# KORUZA_RPi_shield_power.net
KiCad netlist of a schematic drawn in Altium Designer
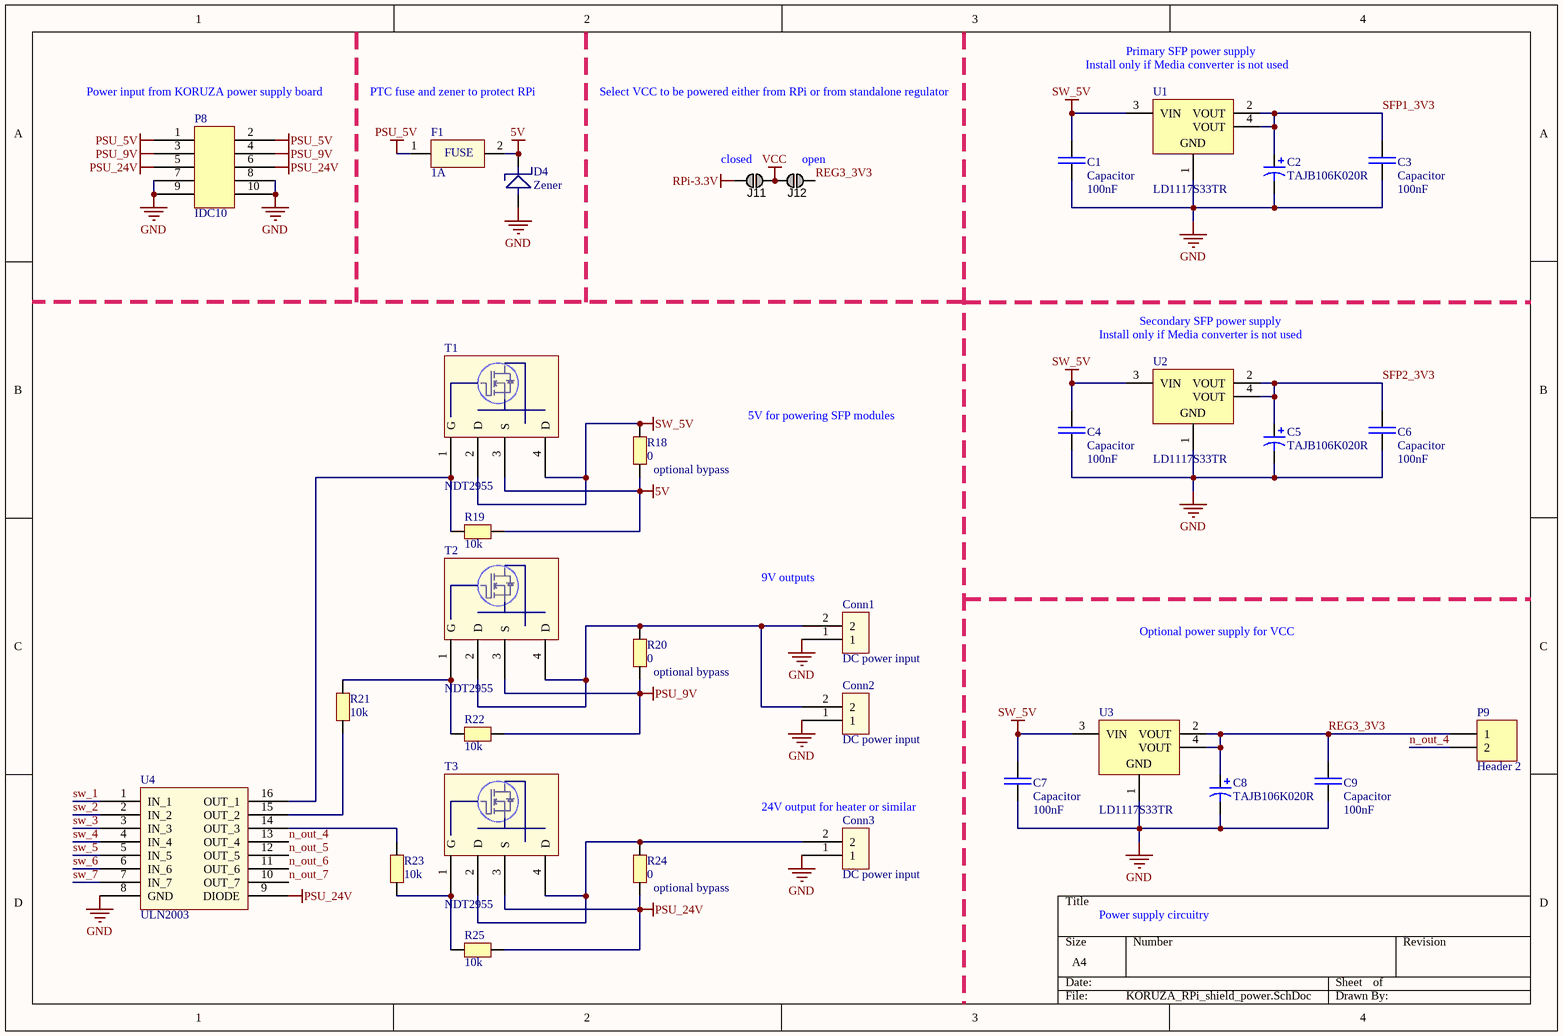
[diagram p0: KORUZA_RPi_shield_power.SchDoc]

(export (version "E")
  (design (tool "Eeschema 10.0.6"))
  (components
    (comp (ref "C1")
      (value "Capacitor")
      (footprint "0603")
      (description "General capacitor")
      (fields (field (name "ALTIUM_VALUE") "100nF"))
      (libsource (lib "GeneralComponents") (part "Capacitor"))
    )
    (comp (ref "C2")
      (value "TAJB106K020R")
      (footprint "AVX-CAPC3528_V")
      (description "Capacitor, Tantalum, 10uF 10% 20V MCCT-B (3528)")
      (fields (field (name "MANUFACTURER") "AVX") (field (name "TOLERANCE") "10%"))
      (libsource (lib "Altium Content Vault") (part "CMP-0279-00001-1"))
    )
    (comp (ref "C3")
      (value "Capacitor")
      (footprint "0603")
      (description "General capacitor")
      (fields (field (name "ALTIUM_VALUE") "100nF"))
      (libsource (lib "GeneralComponents") (part "Capacitor"))
    )
    (comp (ref "C4")
      (value "Capacitor")
      (footprint "0603")
      (description "General capacitor")
      (fields (field (name "ALTIUM_VALUE") "100nF"))
      (libsource (lib "GeneralComponents") (part "Capacitor"))
    )
    (comp (ref "C5")
      (value "TAJB106K020R")
      (footprint "AVX-CAPC3528_V")
      (description "Capacitor, Tantalum, 10uF 10% 20V MCCT-B (3528)")
      (fields (field (name "MANUFACTURER") "AVX") (field (name "TOLERANCE") "10%"))
      (libsource (lib "Altium Content Vault") (part "CMP-0279-00001-1"))
    )
    (comp (ref "C6")
      (value "Capacitor")
      (footprint "0603")
      (description "General capacitor")
      (fields (field (name "ALTIUM_VALUE") "100nF"))
      (libsource (lib "GeneralComponents") (part "Capacitor"))
    )
    (comp (ref "C7")
      (value "Capacitor")
      (footprint "0603")
      (description "General capacitor")
      (fields (field (name "ALTIUM_VALUE") "100nF"))
      (libsource (lib "GeneralComponents") (part "Capacitor"))
    )
    (comp (ref "C8")
      (value "TAJB106K020R")
      (footprint "AVX-CAPC3528_V")
      (description "Capacitor, Tantalum, 10uF 10% 20V MCCT-B (3528)")
      (fields (field (name "MANUFACTURER") "AVX") (field (name "TOLERANCE") "10%"))
      (libsource (lib "Altium Content Vault") (part "CMP-0279-00001-1"))
    )
    (comp (ref "C9")
      (value "Capacitor")
      (footprint "0603")
      (description "General capacitor")
      (fields (field (name "ALTIUM_VALUE") "100nF"))
      (libsource (lib "GeneralComponents") (part "Capacitor"))
    )
    (comp (ref "Conn1")
      (value "DC power input")
      (footprint "MKDSN 2,5/ 2-5,08 and powercon")
      (libsource (lib "GeneralComponents") (part "PowerScrewTerminal"))
    )
    (comp (ref "Conn2")
      (value "DC power input")
      (footprint "MKDSN 2,5/ 2-5,08 and powercon")
      (libsource (lib "GeneralComponents") (part "PowerScrewTerminal"))
    )
    (comp (ref "Conn3")
      (value "DC power input")
      (footprint "MKDSN 2,5/ 2-5,08 and powercon")
      (libsource (lib "GeneralComponents") (part "PowerScrewTerminal"))
    )
    (comp (ref "D4")
      (value "Zener")
      (footprint "DIOMELF3517N")
      (libsource (lib "GeneralComponents") (part "Zener"))
    )
    (comp (ref "F1")
      (value "1A")
      (footprint "1210")
      (description "1A fuse")
      (libsource (lib "GeneralComponents") (part "Fuse"))
    )
    (comp (ref "J11")
      (value "Jumper")
      (footprint "JUMP1")
      (description "SMD jumper")
      (libsource (lib "Misc") (part "JUMP1"))
    )
    (comp (ref "J12")
      (value "Jumper")
      (footprint "JUMP1")
      (description "SMD jumper")
      (libsource (lib "Misc") (part "JUMP1"))
    )
    (comp (ref "P8")
      (value "IDC10")
      (footprint "IDC10")
      (description "IDC 10pin")
      (libsource (lib "GeneralComponents") (part "IDC10"))
    )
    (comp (ref "P9")
      (value "Header 2")
      (footprint "HDR1X2")
      (description "Header, 2-Pin")
      (fields (field (name "PUBLISHER") "Altium Limited"))
      (libsource (lib "Miscellaneous Connectors") (part "Header 2"))
    )
    (comp (ref "R18")
      (value "0")
      (footprint "RESC2012X06N")
      (description "Resistor 0805 smd")
      (libsource (lib "") (part "Resistor_1"))
    )
    (comp (ref "R19")
      (value "10k")
      (footprint "RESC2012X06N")
      (description "Resistor 0805 smd")
      (libsource (lib "GeneralComponents") (part "Resistor"))
    )
    (comp (ref "R20")
      (value "0")
      (footprint "RESC2012X06N")
      (description "Resistor 0805 smd")
      (libsource (lib "") (part "Resistor_1"))
    )
    (comp (ref "R21")
      (value "10k")
      (footprint "RESC2012X06N")
      (description "Resistor 0805 smd")
      (libsource (lib "") (part "Resistor_2"))
    )
    (comp (ref "R22")
      (value "10k")
      (footprint "RESC2012X06N")
      (description "Resistor 0805 smd")
      (libsource (lib "GeneralComponents") (part "Resistor"))
    )
    (comp (ref "R23")
      (value "10k")
      (footprint "RESC2012X06N")
      (description "Resistor 0805 smd")
      (libsource (lib "") (part "Resistor_2"))
    )
    (comp (ref "R24")
      (value "0")
      (footprint "RESC2012X06N")
      (description "Resistor 0805 smd")
      (libsource (lib "") (part "Resistor_1"))
    )
    (comp (ref "R25")
      (value "10k")
      (footprint "RESC2012X06N")
      (description "Resistor 0805 smd")
      (libsource (lib "GeneralComponents") (part "Resistor"))
    )
    (comp (ref "T1")
      (value "NDT2955")
      (footprint "SOT230P700X180-4N")
      (description "P MOSFET")
      (libsource (lib "GeneralComponents") (part "NDT2955"))
    )
    (comp (ref "T2")
      (value "NDT2955")
      (footprint "SOT230P700X180-4N")
      (description "P MOSFET")
      (libsource (lib "GeneralComponents") (part "NDT2955"))
    )
    (comp (ref "T3")
      (value "NDT2955")
      (footprint "SOT230P700X180-4N")
      (description "P MOSFET")
      (libsource (lib "GeneralComponents") (part "NDT2955"))
    )
    (comp (ref "U1")
      (value "LD1117S33TR")
      (footprint "SOT-223_L")
      (description "Fixed Low Drop Positive Voltage Regulator, 3.3V, 4-Pin SOT-223, Tape and Reel")
      (libsource (lib "Altium Content Vault") (part "PM-REG-LD1117-SOT4"))
    )
    (comp (ref "U2")
      (value "LD1117S33TR")
      (footprint "SOT-223_L")
      (description "Fixed Low Drop Positive Voltage Regulator, 3.3V, 4-Pin SOT-223, Tape and Reel")
      (libsource (lib "Altium Content Vault") (part "PM-REG-LD1117-SOT4"))
    )
    (comp (ref "U3")
      (value "LD1117S33TR")
      (footprint "SOT-223_L")
      (description "Fixed Low Drop Positive Voltage Regulator, 3.3V, 4-Pin SOT-223, Tape and Reel")
      (libsource (lib "Altium Content Vault") (part "PM-REG-LD1117-SOT4"))
    )
    (comp (ref "U4")
      (value "ULN2003")
      (footprint "SO-16 narrow")
      (description "Darlington array")
      (libsource (lib "GeneralComponents") (part "ULN2003"))
    )
  )
  (nets
    (net (code "1") (name "/REG3_3V3") (class "Default")
      (node (ref "C8") (pin "1") (pinfunction "1_1") (pintype "passive"))
      (node (ref "C9") (pin "1") (pinfunction "1_1") (pintype "passive"))
      (node (ref "J12") (pin "2") (pintype "passive"))
      (node (ref "P9") (pin "1") (pinfunction "1_1") (pintype "passive"))
      (node (ref "U3") (pin "2") (pinfunction "VOUT_2") (pintype "power_in"))
      (node (ref "U3") (pin "4") (pinfunction "VOUT_4") (pintype "power_in"))
    )
    (net (code "2") (name "/SFP1_3V3") (class "Default")
      (node (ref "C2") (pin "1") (pinfunction "1_1") (pintype "passive"))
      (node (ref "C3") (pin "1") (pinfunction "1_1") (pintype "passive"))
      (node (ref "U1") (pin "2") (pinfunction "VOUT_2") (pintype "power_in"))
      (node (ref "U1") (pin "4") (pinfunction "VOUT_4") (pintype "power_in"))
    )
    (net (code "3") (name "/SFP2_3V3") (class "Default")
      (node (ref "C5") (pin "1") (pinfunction "1_1") (pintype "passive"))
      (node (ref "C6") (pin "1") (pinfunction "1_1") (pintype "passive"))
      (node (ref "U2") (pin "2") (pinfunction "VOUT_2") (pintype "power_in"))
      (node (ref "U2") (pin "4") (pinfunction "VOUT_4") (pintype "power_in"))
    )
    (net (code "4") (name "/n_out_4") (class "Default")
      (node (ref "P9") (pin "2") (pinfunction "2_2") (pintype "passive"))
      (node (ref "U4") (pin "13") (pinfunction "OUT_4_13") (pintype "passive"))
    )
    (net (code "5") (name "/n_out_5") (class "Default")
      (node (ref "U4") (pin "12") (pinfunction "OUT_5_12") (pintype "passive"))
    )
    (net (code "6") (name "/n_out_6") (class "Default")
      (node (ref "U4") (pin "11") (pinfunction "OUT_6_11") (pintype "passive"))
    )
    (net (code "7") (name "/n_out_7") (class "Default")
      (node (ref "U4") (pin "10") (pinfunction "OUT_7_10") (pintype "passive"))
    )
    (net (code "8") (name "/sw_1") (class "Default")
      (node (ref "U4") (pin "1") (pinfunction "IN_1_1") (pintype "passive"))
    )
    (net (code "9") (name "/sw_2") (class "Default")
      (node (ref "U4") (pin "2") (pinfunction "IN_2_2") (pintype "passive"))
    )
    (net (code "10") (name "/sw_3") (class "Default")
      (node (ref "U4") (pin "3") (pinfunction "IN_3_3") (pintype "passive"))
    )
    (net (code "11") (name "/sw_4") (class "Default")
      (node (ref "U4") (pin "4") (pinfunction "IN_4_4") (pintype "passive"))
    )
    (net (code "12") (name "/sw_5") (class "Default")
      (node (ref "U4") (pin "5") (pinfunction "IN_5_5") (pintype "passive"))
    )
    (net (code "13") (name "/sw_6") (class "Default")
      (node (ref "U4") (pin "6") (pinfunction "IN_6_6") (pintype "passive"))
    )
    (net (code "14") (name "/sw_7") (class "Default")
      (node (ref "U4") (pin "7") (pinfunction "IN_7_7") (pintype "passive"))
    )
    (net (code "15") (name "5V") (class "Default")
      (node (ref "D4") (pin "1") (pinfunction "1_1") (pintype "passive"))
      (node (ref "F1") (pin "2") (pintype "power_in"))
      (node (ref "R18") (pin "2") (pinfunction "2_2") (pintype "passive"))
      (node (ref "R19") (pin "2") (pinfunction "2_2") (pintype "passive"))
      (node (ref "T1") (pin "3") (pinfunction "S_3") (pintype "passive"))
    )
    (net (code "16") (name "GND") (class "Default")
      (node (ref "C1") (pin "2") (pinfunction "2_2") (pintype "passive"))
      (node (ref "C2") (pin "2") (pinfunction "2_2") (pintype "passive"))
      (node (ref "C3") (pin "2") (pinfunction "2_2") (pintype "passive"))
      (node (ref "C4") (pin "2") (pinfunction "2_2") (pintype "passive"))
      (node (ref "C5") (pin "2") (pinfunction "2_2") (pintype "passive"))
      (node (ref "C6") (pin "2") (pinfunction "2_2") (pintype "passive"))
      (node (ref "C7") (pin "2") (pinfunction "2_2") (pintype "passive"))
      (node (ref "C8") (pin "2") (pinfunction "2_2") (pintype "passive"))
      (node (ref "C9") (pin "2") (pinfunction "2_2") (pintype "passive"))
      (node (ref "Conn1") (pin "1") (pinfunction "1_1") (pintype "passive"))
      (node (ref "Conn2") (pin "1") (pinfunction "1_1") (pintype "passive"))
      (node (ref "Conn3") (pin "1") (pinfunction "1_1") (pintype "passive"))
      (node (ref "D4") (pin "2") (pinfunction "2_2") (pintype "passive"))
      (node (ref "P8") (pin "10") (pinfunction "10_10") (pintype "passive"))
      (node (ref "P8") (pin "7") (pinfunction "7_7") (pintype "passive"))
      (node (ref "P8") (pin "8") (pinfunction "8_8") (pintype "passive"))
      (node (ref "P8") (pin "9") (pinfunction "9_9") (pintype "passive"))
      (node (ref "U1") (pin "1") (pinfunction "GND_1") (pintype "power_in"))
      (node (ref "U2") (pin "1") (pinfunction "GND_1") (pintype "power_in"))
      (node (ref "U3") (pin "1") (pinfunction "GND_1") (pintype "power_in"))
      (node (ref "U4") (pin "8") (pinfunction "GND_8") (pintype "passive"))
    )
    (net (code "17") (name "Net-(Conn1-Pad2)") (class "Default")
      (node (ref "Conn1") (pin "2") (pinfunction "2_2") (pintype "passive"))
      (node (ref "Conn2") (pin "2") (pinfunction "2_2") (pintype "passive"))
      (node (ref "R20") (pin "1") (pinfunction "1_1") (pintype "passive"))
      (node (ref "T2") (pin "2") (pinfunction "D_2") (pintype "passive"))
      (node (ref "T2") (pin "4") (pinfunction "D_4") (pintype "passive"))
    )
    (net (code "18") (name "Net-(Conn3-Pad2)") (class "Default")
      (node (ref "Conn3") (pin "2") (pinfunction "2_2") (pintype "passive"))
      (node (ref "R24") (pin "1") (pinfunction "1_1") (pintype "passive"))
      (node (ref "T3") (pin "2") (pinfunction "D_2") (pintype "passive"))
      (node (ref "T3") (pin "4") (pinfunction "D_4") (pintype "passive"))
    )
    (net (code "19") (name "Net-(T1-G)") (class "Default")
      (node (ref "R19") (pin "1") (pinfunction "1_1") (pintype "passive"))
      (node (ref "T1") (pin "1") (pinfunction "G_1") (pintype "passive"))
      (node (ref "U4") (pin "16") (pinfunction "OUT_1_16") (pintype "passive"))
    )
    (net (code "20") (name "Net-(T2-G)") (class "Default")
      (node (ref "R21") (pin "2") (pinfunction "2_2") (pintype "passive"))
      (node (ref "R22") (pin "1") (pinfunction "1_1") (pintype "passive"))
      (node (ref "T2") (pin "1") (pinfunction "G_1") (pintype "passive"))
    )
    (net (code "21") (name "Net-(T3-G)") (class "Default")
      (node (ref "R23") (pin "1") (pinfunction "1_1") (pintype "passive"))
      (node (ref "R25") (pin "1") (pinfunction "1_1") (pintype "passive"))
      (node (ref "T3") (pin "1") (pinfunction "G_1") (pintype "passive"))
    )
    (net (code "22") (name "Net-(U4-OUT_2)") (class "Default")
      (node (ref "R21") (pin "1") (pinfunction "1_1") (pintype "passive"))
      (node (ref "U4") (pin "15") (pinfunction "OUT_2_15") (pintype "passive"))
    )
    (net (code "23") (name "Net-(U4-OUT_3)") (class "Default")
      (node (ref "R23") (pin "2") (pinfunction "2_2") (pintype "passive"))
      (node (ref "U4") (pin "14") (pinfunction "OUT_3_14") (pintype "passive"))
    )
    (net (code "24") (name "PSU_5V") (class "Default")
      (node (ref "F1") (pin "1") (pintype "power_in"))
      (node (ref "P8") (pin "1") (pinfunction "A_1") (pintype "passive"))
      (node (ref "P8") (pin "2") (pinfunction "2_2") (pintype "passive"))
    )
    (net (code "25") (name "PSU_9V") (class "Default")
      (node (ref "P8") (pin "3") (pinfunction "3_3") (pintype "passive"))
      (node (ref "P8") (pin "4") (pinfunction "4_4") (pintype "passive"))
      (node (ref "R20") (pin "2") (pinfunction "2_2") (pintype "passive"))
      (node (ref "R22") (pin "2") (pinfunction "2_2") (pintype "passive"))
      (node (ref "T2") (pin "3") (pinfunction "S_3") (pintype "passive"))
    )
    (net (code "26") (name "PSU_24V") (class "Default")
      (node (ref "P8") (pin "5") (pinfunction "5_5") (pintype "passive"))
      (node (ref "P8") (pin "6") (pinfunction "6_6") (pintype "passive"))
      (node (ref "R24") (pin "2") (pinfunction "2_2") (pintype "passive"))
      (node (ref "R25") (pin "2") (pinfunction "2_2") (pintype "passive"))
      (node (ref "T3") (pin "3") (pinfunction "S_3") (pintype "passive"))
      (node (ref "U4") (pin "9") (pinfunction "DIODE_9") (pintype "passive"))
    )
    (net (code "27") (name "RPi-3.3V") (class "Default") (node (ref "J11") (pin "1") (pintype "passive")))
    (net (code "28") (name "SW_5V") (class "Default")
      (node (ref "C1") (pin "1") (pinfunction "1_1") (pintype "passive"))
      (node (ref "C4") (pin "1") (pinfunction "1_1") (pintype "passive"))
      (node (ref "C7") (pin "1") (pinfunction "1_1") (pintype "passive"))
      (node (ref "R18") (pin "1") (pinfunction "1_1") (pintype "passive"))
      (node (ref "T1") (pin "2") (pinfunction "D_2") (pintype "passive"))
      (node (ref "T1") (pin "4") (pinfunction "D_4") (pintype "passive"))
      (node (ref "U1") (pin "3") (pinfunction "VIN_3") (pintype "power_in"))
      (node (ref "U2") (pin "3") (pinfunction "VIN_3") (pintype "power_in"))
      (node (ref "U3") (pin "3") (pinfunction "VIN_3") (pintype "power_in"))
    )
    (net (code "29") (name "VCC") (class "Default")
      (node (ref "J11") (pin "2") (pintype "passive"))
      (node (ref "J12") (pin "1") (pintype "passive"))
    )
  )
)
